# wordclock_v1_9.net
KiCad netlist of a schematic drawn in EAGLE
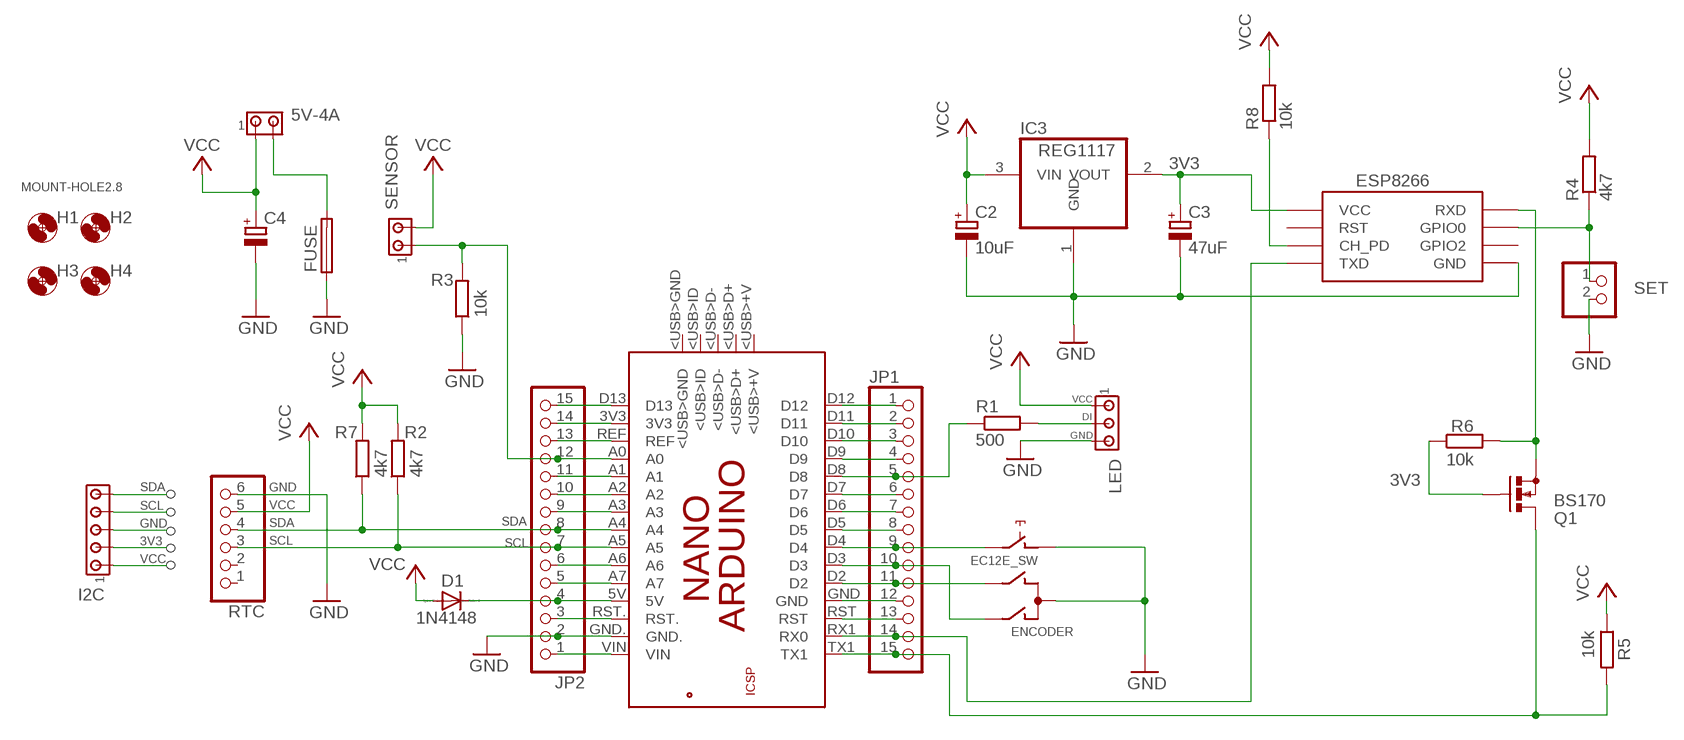
[diagram p0: schematic, sheet 1]

(export (version "E")
  (design (tool "Eeschema 10.0.6"))
  (components
    (comp (ref "5V-4A")
      (value "5V-4A")
      (footprint "eagle-import:1X2MTA")
      (libsource (lib "eagle-import") (part "MTA02-156"))
    )
    (comp (ref "C2")
      (value "10uF")
      (footprint "eagle-import:B45181A")
      (libsource (lib "eagle-import") (part "CPOL-EUB45181A"))
    )
    (comp (ref "C3")
      (value "47uF")
      (footprint "eagle-import:B45181A")
      (libsource (lib "eagle-import") (part "CPOL-EUB45181A"))
    )
    (comp (ref "C4")
      (value "CPOL-EUE5-10.5")
      (footprint "eagle-import:E5-10,5")
      (libsource (lib "eagle-import") (part "CPOL-EUE5-10.5"))
    )
    (comp (ref "D1")
      (value "1N4148")
      (footprint "eagle-import:DO35-10")
      (libsource (lib "eagle-import") (part "1N4148DO35-10"))
    )
    (comp (ref "ENCODER")
      (value "EC12E_SW")
      (footprint "eagle-import:ALPS_EC12E_SW")
      (fields (field (name "MPN") "EC12E2424407"))
      (libsource (lib "eagle-import") (part "EC12E_SW"))
    )
    (comp (ref "ESP8266")
      (value "ESP01")
      (footprint "eagle-import:ESP01")
      (libsource (lib "eagle-import") (part "ESP01"))
    )
    (comp (ref "FUSE")
      (value "FUSELITTLEFUSE")
      (footprint "eagle-import:LITTLEFUSE")
      (libsource (lib "eagle-import") (part "FUSELITTLEFUSE"))
    )
    (comp (ref "H1")
      (value "MOUNT-HOLE2.8")
      (footprint "eagle-import:2,8")
      (libsource (lib "eagle-import") (part "MOUNT-HOLE2.8"))
    )
    (comp (ref "H2")
      (value "MOUNT-HOLE2.8")
      (footprint "eagle-import:2,8")
      (libsource (lib "eagle-import") (part "MOUNT-HOLE2.8"))
    )
    (comp (ref "H3")
      (value "MOUNT-HOLE2.8")
      (footprint "eagle-import:2,8")
      (libsource (lib "eagle-import") (part "MOUNT-HOLE2.8"))
    )
    (comp (ref "H4")
      (value "MOUNT-HOLE2.8")
      (footprint "eagle-import:2,8")
      (libsource (lib "eagle-import") (part "MOUNT-HOLE2.8"))
    )
    (comp (ref "I2C")
      (value "MTA05-100")
      (footprint "eagle-import:10X05MTA")
      (libsource (lib "eagle-import") (part "MTA05-100"))
    )
    (comp (ref "IC3")
      (value "REG1117")
      (footprint "eagle-import:SOT223")
      (libsource (lib "eagle-import") (part "REG1117"))
    )
    (comp (ref "JP1")
      (value "PINHD-1X15")
      (footprint "eagle-import:1X15")
      (libsource (lib "eagle-import") (part "PINHD-1X15"))
    )
    (comp (ref "JP2")
      (value "PINHD-1X15")
      (footprint "eagle-import:1X15")
      (libsource (lib "eagle-import") (part "PINHD-1X15"))
    )
    (comp (ref "LED")
      (value "MTA03-156")
      (footprint "eagle-import:1X3MTA")
      (libsource (lib "eagle-import") (part "MTA03-156"))
    )
    (comp (ref "PCB2")
      (value "ARDUINO_NANO")
      (footprint "eagle-import:ARDUINO_NANO")
      (libsource (lib "eagle-import") (part "ARDUINO_NANO"))
    )
    (comp (ref "Q1")
      (value "BS170")
      (footprint "eagle-import:SOT54E")
      (libsource (lib "eagle-import") (part "BS170"))
    )
    (comp (ref "R1")
      (value "500")
      (footprint "eagle-import:0207_7")
      (libsource (lib "eagle-import") (part "resistor_R-EU_0207/7"))
    )
    (comp (ref "R2")
      (value "4k7")
      (footprint "eagle-import:0207_10")
      (libsource (lib "eagle-import") (part "R-EU_0207/10"))
    )
    (comp (ref "R3")
      (value "10k")
      (footprint "eagle-import:0207_10")
      (libsource (lib "eagle-import") (part "R-EU_0207/10"))
    )
    (comp (ref "R4")
      (value "4k7")
      (footprint "eagle-import:0207_10")
      (libsource (lib "eagle-import") (part "R-EU_0207/10"))
    )
    (comp (ref "R5")
      (value "10k")
      (footprint "eagle-import:0207_10")
      (libsource (lib "eagle-import") (part "R-EU_0207/10"))
    )
    (comp (ref "R6")
      (value "10k")
      (footprint "eagle-import:0207_10")
      (libsource (lib "eagle-import") (part "R-EU_0207/10"))
    )
    (comp (ref "R7")
      (value "4k7")
      (footprint "eagle-import:0207_10")
      (libsource (lib "eagle-import") (part "R-EU_0207/10"))
    )
    (comp (ref "R8")
      (value "10k")
      (footprint "eagle-import:0207_10")
      (libsource (lib "eagle-import") (part "R-EU_0207/10"))
    )
    (comp (ref "RTC")
      (value "PINHD-1X6")
      (footprint "eagle-import:1X06")
      (libsource (lib "eagle-import") (part "PINHD-1X6"))
    )
    (comp (ref "SENSOR")
      (value "MTA02-156")
      (footprint "eagle-import:1X2MTA")
      (libsource (lib "eagle-import") (part "MTA02-156"))
    )
    (comp (ref "SET")
      (value "PINHD-1X2")
      (footprint "eagle-import:1X02")
      (libsource (lib "eagle-import") (part "PINHD-1X2"))
    )
  )
  (nets
    (net (code "1") (name "3V3") (class "Default")
      (node (ref "C3") (pin "+") (pinfunction "+_+") (pintype "passive"))
      (node (ref "ESP8266") (pin "VCC") (pinfunction "VCC_VCC") (pintype "bidirectional"))
      (node (ref "I2C") (pin "2") (pinfunction "2_2") (pintype "passive"))
      (node (ref "IC3") (pin "2") (pinfunction "VOUT_2") (pintype "output"))
      (node (ref "Q1") (pin "G") (pinfunction "G_G") (pintype "passive"))
      (node (ref "R6") (pin "1") (pinfunction "1_1") (pintype "passive"))
    )
    (net (code "2") (name "DI") (class "Default")
      (node (ref "LED") (pin "2") (pinfunction "2_2") (pintype "passive"))
      (node (ref "R1") (pin "2") (pinfunction "2_2") (pintype "passive"))
    )
    (net (code "3") (name "GND") (class "Default")
      (node (ref "C2") (pin "-") (pinfunction "-_-") (pintype "passive"))
      (node (ref "C3") (pin "-") (pinfunction "-_-") (pintype "passive"))
      (node (ref "C4") (pin "-") (pinfunction "-_-") (pintype "passive"))
      (node (ref "ENCODER") (pin "C") (pinfunction "C_C") (pintype "passive"))
      (node (ref "ENCODER") (pin "D") (pinfunction "1_D") (pintype "passive"))
      (node (ref "ESP8266") (pin "GND") (pinfunction "GND_GND") (pintype "bidirectional"))
      (node (ref "FUSE") (pin "1") (pinfunction "1_1") (pintype "passive"))
      (node (ref "I2C") (pin "3") (pinfunction "3_3") (pintype "passive"))
      (node (ref "IC3") (pin "1") (pinfunction "GND_1") (pintype "power_in"))
      (node (ref "JP2") (pin "2") (pinfunction "2_2") (pintype "passive"))
      (node (ref "LED") (pin "3") (pinfunction "3_3") (pintype "passive"))
      (node (ref "PCB2") (pin "GND.") (pinfunction "GND._GND.") (pintype "bidirectional"))
      (node (ref "R3") (pin "1") (pinfunction "1_1") (pintype "passive"))
      (node (ref "RTC") (pin "6") (pinfunction "6_6") (pintype "passive"))
      (node (ref "SET") (pin "2") (pinfunction "2_2") (pintype "passive"))
    )
    (net (code "4") (name "Net-(5V-4A-Pad2)") (class "Default")
      (node (ref "5V-4A") (pin "2") (pinfunction "2_2") (pintype "passive"))
      (node (ref "FUSE") (pin "2") (pinfunction "2_2") (pintype "passive"))
    )
    (net (code "5") (name "Net-(D1-PadC)") (class "Default")
      (node (ref "D1") (pin "C") (pinfunction "C_C") (pintype "passive"))
      (node (ref "JP2") (pin "4") (pinfunction "4_4") (pintype "passive"))
      (node (ref "PCB2") (pin "5V") (pinfunction "5V_5V") (pintype "bidirectional"))
    )
    (net (code "6") (name "Net-(ENCODER-PadA)") (class "Default")
      (node (ref "ENCODER") (pin "A") (pinfunction "A_A") (pintype "passive"))
      (node (ref "JP1") (pin "10") (pinfunction "10_10") (pintype "passive"))
      (node (ref "PCB2") (pin "D3") (pinfunction "D3_D3") (pintype "bidirectional"))
    )
    (net (code "7") (name "Net-(ENCODER-PadB)") (class "Default")
      (node (ref "ENCODER") (pin "B") (pinfunction "B_B") (pintype "passive"))
      (node (ref "JP1") (pin "11") (pinfunction "11_11") (pintype "passive"))
      (node (ref "PCB2") (pin "D2") (pinfunction "D2_D2") (pintype "bidirectional"))
    )
    (net (code "8") (name "Net-(ENCODERB-2)") (class "Default")
      (node (ref "ENCODER") (pin "E") (pinfunction "2_E") (pintype "passive"))
      (node (ref "JP1") (pin "9") (pinfunction "9_9") (pintype "passive"))
      (node (ref "PCB2") (pin "D4") (pinfunction "D4_D4") (pintype "bidirectional"))
    )
    (net (code "9") (name "Net-(ESP8266-PadCH_PD)") (class "Default")
      (node (ref "ESP8266") (pin "CH_PD") (pinfunction "CH_PD_CH_PD") (pintype "bidirectional"))
      (node (ref "R8") (pin "1") (pinfunction "1_1") (pintype "passive"))
    )
    (net (code "10") (name "Net-(ESP8266-PadGPIO0)") (class "Default")
      (node (ref "ESP8266") (pin "GPIO0") (pinfunction "GPIO0_GPIO0") (pintype "bidirectional"))
      (node (ref "R4") (pin "1") (pinfunction "1_1") (pintype "passive"))
      (node (ref "SET") (pin "1") (pinfunction "1_1") (pintype "passive"))
    )
    (net (code "11") (name "Net-(ESP8266-RXD)") (class "Default")
      (node (ref "ESP8266") (pin "RX") (pinfunction "RXD_RX") (pintype "bidirectional"))
      (node (ref "Q1") (pin "S") (pinfunction "S_S") (pintype "passive"))
      (node (ref "R6") (pin "2") (pinfunction "2_2") (pintype "passive"))
    )
    (net (code "12") (name "Net-(ESP8266-TXD)") (class "Default")
      (node (ref "ESP8266") (pin "TX") (pinfunction "TXD_TX") (pintype "bidirectional"))
      (node (ref "JP1") (pin "14") (pinfunction "14_14") (pintype "passive"))
      (node (ref "PCB2") (pin "RX1") (pinfunction "RX0_RX1") (pintype "bidirectional"))
    )
    (net (code "13") (name "Net-(JP1-Pad1)") (class "Default")
      (node (ref "JP1") (pin "1") (pinfunction "1_1") (pintype "passive"))
      (node (ref "PCB2") (pin "D12") (pinfunction "D12_D12") (pintype "bidirectional"))
    )
    (net (code "14") (name "Net-(JP1-Pad2)") (class "Default")
      (node (ref "JP1") (pin "2") (pinfunction "2_2") (pintype "passive"))
      (node (ref "PCB2") (pin "D11") (pinfunction "D11_D11") (pintype "bidirectional"))
    )
    (net (code "15") (name "Net-(JP1-Pad3)") (class "Default")
      (node (ref "JP1") (pin "3") (pinfunction "3_3") (pintype "passive"))
      (node (ref "PCB2") (pin "D10") (pinfunction "D10_D10") (pintype "bidirectional"))
    )
    (net (code "16") (name "Net-(JP1-Pad4)") (class "Default")
      (node (ref "JP1") (pin "4") (pinfunction "4_4") (pintype "passive"))
      (node (ref "PCB2") (pin "D9") (pinfunction "D9_D9") (pintype "bidirectional"))
    )
    (net (code "17") (name "Net-(JP1-Pad5)") (class "Default")
      (node (ref "JP1") (pin "5") (pinfunction "5_5") (pintype "passive"))
      (node (ref "PCB2") (pin "D8") (pinfunction "D8_D8") (pintype "bidirectional"))
      (node (ref "R1") (pin "1") (pinfunction "1_1") (pintype "passive"))
    )
    (net (code "18") (name "Net-(JP1-Pad6)") (class "Default")
      (node (ref "JP1") (pin "6") (pinfunction "6_6") (pintype "passive"))
      (node (ref "PCB2") (pin "D7") (pinfunction "D7_D7") (pintype "bidirectional"))
    )
    (net (code "19") (name "Net-(JP1-Pad7)") (class "Default")
      (node (ref "JP1") (pin "7") (pinfunction "7_7") (pintype "passive"))
      (node (ref "PCB2") (pin "D6") (pinfunction "D6_D6") (pintype "bidirectional"))
    )
    (net (code "20") (name "Net-(JP1-Pad8)") (class "Default")
      (node (ref "JP1") (pin "8") (pinfunction "8_8") (pintype "passive"))
      (node (ref "PCB2") (pin "D5") (pinfunction "D5_D5") (pintype "bidirectional"))
    )
    (net (code "21") (name "Net-(JP1-Pad12)") (class "Default")
      (node (ref "JP1") (pin "12") (pinfunction "12_12") (pintype "passive"))
      (node (ref "PCB2") (pin "GND") (pinfunction "GND_GND") (pintype "bidirectional"))
    )
    (net (code "22") (name "Net-(JP1-Pad13)") (class "Default")
      (node (ref "JP1") (pin "13") (pinfunction "13_13") (pintype "passive"))
      (node (ref "PCB2") (pin "RST") (pinfunction "RST_RST") (pintype "bidirectional"))
    )
    (net (code "23") (name "Net-(JP1-Pad15)") (class "Default")
      (node (ref "JP1") (pin "15") (pinfunction "15_15") (pintype "passive"))
      (node (ref "PCB2") (pin "TX1") (pinfunction "TX1_TX1") (pintype "bidirectional"))
      (node (ref "Q1") (pin "D") (pinfunction "D_D") (pintype "passive"))
      (node (ref "R5") (pin "2") (pinfunction "2_2") (pintype "passive"))
    )
    (net (code "24") (name "Net-(JP2-Pad1)") (class "Default")
      (node (ref "JP2") (pin "1") (pinfunction "1_1") (pintype "passive"))
      (node (ref "PCB2") (pin "VIN") (pinfunction "VIN_VIN") (pintype "bidirectional"))
    )
    (net (code "25") (name "Net-(JP2-Pad3)") (class "Default")
      (node (ref "JP2") (pin "3") (pinfunction "3_3") (pintype "passive"))
      (node (ref "PCB2") (pin "RST.") (pinfunction "RST._RST.") (pintype "bidirectional"))
    )
    (net (code "26") (name "Net-(JP2-Pad5)") (class "Default")
      (node (ref "JP2") (pin "5") (pinfunction "5_5") (pintype "passive"))
      (node (ref "PCB2") (pin "A7") (pinfunction "A7_A7") (pintype "bidirectional"))
    )
    (net (code "27") (name "Net-(JP2-Pad6)") (class "Default")
      (node (ref "JP2") (pin "6") (pinfunction "6_6") (pintype "passive"))
      (node (ref "PCB2") (pin "A6") (pinfunction "A6_A6") (pintype "bidirectional"))
    )
    (net (code "28") (name "Net-(JP2-Pad9)") (class "Default")
      (node (ref "JP2") (pin "9") (pinfunction "9_9") (pintype "passive"))
      (node (ref "PCB2") (pin "A3") (pinfunction "A3_A3") (pintype "bidirectional"))
    )
    (net (code "29") (name "Net-(JP2-Pad10)") (class "Default")
      (node (ref "JP2") (pin "10") (pinfunction "10_10") (pintype "passive"))
      (node (ref "PCB2") (pin "A2") (pinfunction "A2_A2") (pintype "bidirectional"))
    )
    (net (code "30") (name "Net-(JP2-Pad11)") (class "Default")
      (node (ref "JP2") (pin "11") (pinfunction "11_11") (pintype "passive"))
      (node (ref "PCB2") (pin "A1") (pinfunction "A1_A1") (pintype "bidirectional"))
    )
    (net (code "31") (name "Net-(JP2-Pad12)") (class "Default")
      (node (ref "JP2") (pin "12") (pinfunction "12_12") (pintype "passive"))
      (node (ref "PCB2") (pin "A0") (pinfunction "A0_A0") (pintype "bidirectional"))
      (node (ref "R3") (pin "2") (pinfunction "2_2") (pintype "passive"))
      (node (ref "SENSOR") (pin "1") (pinfunction "1_1") (pintype "passive"))
    )
    (net (code "32") (name "Net-(JP2-Pad13)") (class "Default")
      (node (ref "JP2") (pin "13") (pinfunction "13_13") (pintype "passive"))
      (node (ref "PCB2") (pin "REF") (pinfunction "REF_REF") (pintype "bidirectional"))
    )
    (net (code "33") (name "Net-(JP2-Pad14)") (class "Default")
      (node (ref "JP2") (pin "14") (pinfunction "14_14") (pintype "passive"))
      (node (ref "PCB2") (pin "3V3") (pinfunction "3V3_3V3") (pintype "bidirectional"))
    )
    (net (code "34") (name "Net-(JP2-Pad15)") (class "Default")
      (node (ref "JP2") (pin "15") (pinfunction "15_15") (pintype "passive"))
      (node (ref "PCB2") (pin "D13") (pinfunction "D13_D13") (pintype "bidirectional"))
    )
    (net (code "35") (name "SCL") (class "Default")
      (node (ref "I2C") (pin "4") (pinfunction "4_4") (pintype "passive"))
      (node (ref "JP2") (pin "7") (pinfunction "7_7") (pintype "passive"))
      (node (ref "PCB2") (pin "A5") (pinfunction "A5_A5") (pintype "bidirectional"))
      (node (ref "R2") (pin "1") (pinfunction "1_1") (pintype "passive"))
      (node (ref "RTC") (pin "3") (pinfunction "3_3") (pintype "passive"))
    )
    (net (code "36") (name "SDA") (class "Default")
      (node (ref "I2C") (pin "5") (pinfunction "5_5") (pintype "passive"))
      (node (ref "JP2") (pin "8") (pinfunction "8_8") (pintype "passive"))
      (node (ref "PCB2") (pin "A4") (pinfunction "A4_A4") (pintype "bidirectional"))
      (node (ref "R7") (pin "1") (pinfunction "1_1") (pintype "passive"))
      (node (ref "RTC") (pin "4") (pinfunction "4_4") (pintype "passive"))
    )
    (net (code "37") (name "VCC") (class "Default")
      (node (ref "5V-4A") (pin "1") (pinfunction "1_1") (pintype "passive"))
      (node (ref "C2") (pin "+") (pinfunction "+_+") (pintype "passive"))
      (node (ref "C4") (pin "+") (pinfunction "+_+") (pintype "passive"))
      (node (ref "D1") (pin "A") (pinfunction "A_A") (pintype "passive"))
      (node (ref "I2C") (pin "1") (pinfunction "1_1") (pintype "passive"))
      (node (ref "IC3") (pin "3") (pinfunction "VIN_3") (pintype "input"))
      (node (ref "LED") (pin "1") (pinfunction "1_1") (pintype "passive"))
      (node (ref "R2") (pin "2") (pinfunction "2_2") (pintype "passive"))
      (node (ref "R4") (pin "2") (pinfunction "2_2") (pintype "passive"))
      (node (ref "R5") (pin "1") (pinfunction "1_1") (pintype "passive"))
      (node (ref "R7") (pin "2") (pinfunction "2_2") (pintype "passive"))
      (node (ref "R8") (pin "2") (pinfunction "2_2") (pintype "passive"))
      (node (ref "RTC") (pin "5") (pinfunction "5_5") (pintype "passive"))
      (node (ref "SENSOR") (pin "2") (pinfunction "2_2") (pintype "passive"))
    )
    (net (code "38") (name "unconnected-(ESP8266-PadGPIO2)") (class "Default")
      (node (ref "ESP8266") (pin "GPIO2") (pinfunction "GPIO2_GPIO2") (pintype "bidirectional"))
    )
    (net (code "39") (name "unconnected-(ESP8266-PadRST)") (class "Default")
      (node (ref "ESP8266") (pin "RST") (pinfunction "RST_RST") (pintype "bidirectional"))
    )
    (net (code "40") (name "unconnected-(PCB2-Pad5V.)") (class "Default")
      (node (ref "PCB2") (pin "5V.") (pinfunction "5V._5V.") (pintype "bidirectional"))
    )
    (net (code "41") (name "unconnected-(PCB2-Pad<USB>+V)") (class "Default")
      (node (ref "PCB2") (pin "<USB>+V") (pinfunction "<USB>+V_<USB>+V") (pintype "bidirectional"))
    )
    (net (code "42") (name "unconnected-(PCB2-Pad<USB>D+)") (class "Default")
      (node (ref "PCB2") (pin "<USB>D+") (pinfunction "<USB>D+_<USB>D+") (pintype "bidirectional"))
    )
    (net (code "43") (name "unconnected-(PCB2-Pad<USB>D-)") (class "Default")
      (node (ref "PCB2") (pin "<USB>D-") (pinfunction "<USB>D-_<USB>D-") (pintype "bidirectional"))
    )
    (net (code "44") (name "unconnected-(PCB2-Pad<USB>GND)") (class "Default")
      (node (ref "PCB2") (pin "<USB>GND") (pinfunction "<USB>GND_<USB>GND") (pintype "bidirectional"))
    )
    (net (code "45") (name "unconnected-(PCB2-Pad<USB>ID)") (class "Default")
      (node (ref "PCB2") (pin "<USB>ID") (pinfunction "<USB>ID_<USB>ID") (pintype "bidirectional"))
    )
    (net (code "46") (name "unconnected-(PCB2-PadGND_)") (class "Default")
      (node (ref "PCB2") (pin "GND_") (pinfunction "GND__GND_") (pintype "bidirectional"))
    )
    (net (code "47") (name "unconnected-(PCB2-PadMISO)") (class "Default")
      (node (ref "PCB2") (pin "MISO") (pinfunction "MISO_MISO") (pintype "bidirectional"))
    )
    (net (code "48") (name "unconnected-(PCB2-PadMOSI)") (class "Default")
      (node (ref "PCB2") (pin "MOSI") (pinfunction "MOSI_MOSI") (pintype "bidirectional"))
    )
    (net (code "49") (name "unconnected-(PCB2-PadRESET..)") (class "Default")
      (node (ref "PCB2") (pin "RESET..") (pinfunction "RESET.._RESET..") (pintype "bidirectional"))
    )
    (net (code "50") (name "unconnected-(PCB2-PadSCK)") (class "Default")
      (node (ref "PCB2") (pin "SCK") (pinfunction "SCK_SCK") (pintype "bidirectional"))
    )
    (net (code "51") (name "unconnected-(RTC-Pad1)") (class "Default")
      (node (ref "RTC") (pin "1") (pinfunction "1_1") (pintype "passive"))
    )
    (net (code "52") (name "unconnected-(RTC-Pad2)") (class "Default")
      (node (ref "RTC") (pin "2") (pinfunction "2_2") (pintype "passive"))
    )
  )
)
